# Waveform_Gen_V1_0.net
KiCad netlist of a schematic drawn in EAGLE
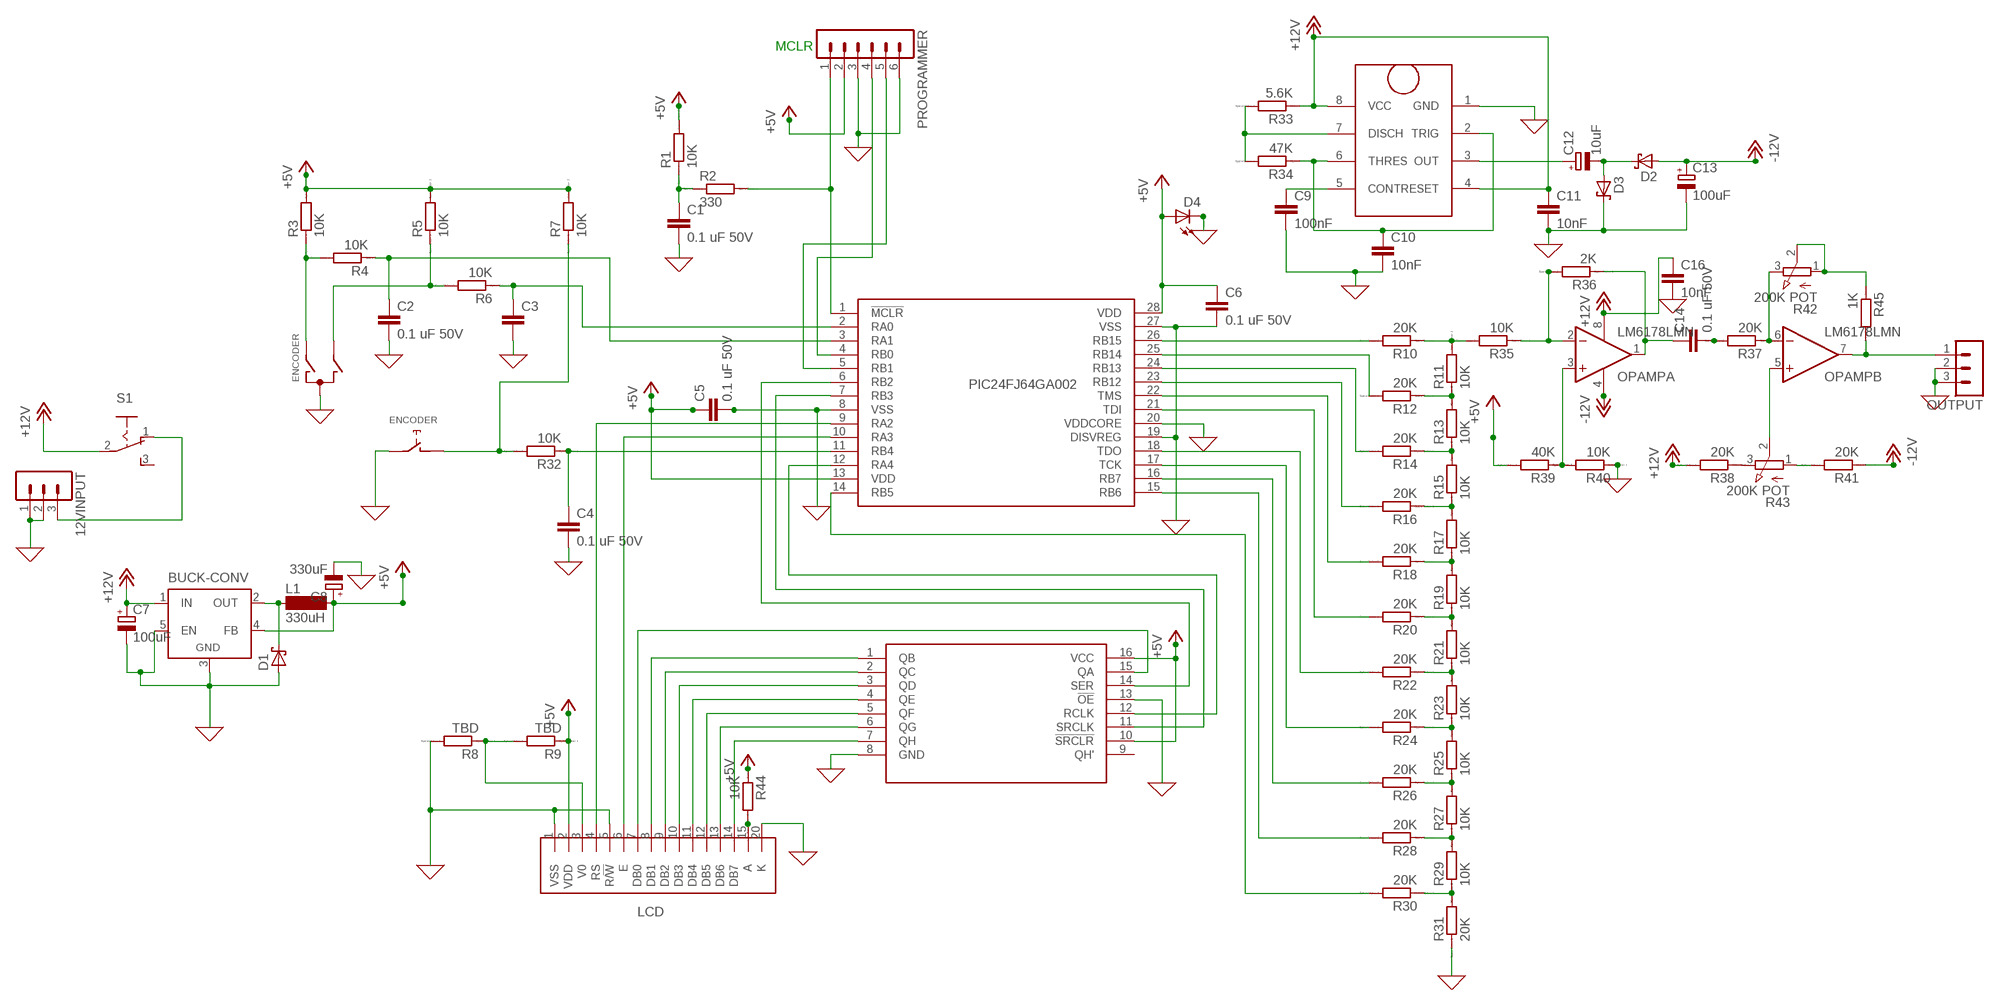
[diagram p0: schematic, sheet 1]

(export (version "E")
  (design (tool "Eeschema 10.0.6"))
  (components
    (comp (ref "12VINPUT")
      (value "MA03-1")
      (footprint "eagle-import:MA03-1")
      (libsource (lib "eagle-import") (part "MA03-1"))
    )
    (comp (ref "BUCK-CONV")
      (value "LM2596TH")
      (footprint "eagle-import:TO220-52")
      (libsource (lib "eagle-import") (part "LM2596TH"))
    )
    (comp (ref "C1")
      (value "0.1 uF 50V")
      (footprint "eagle-import:C5B2.5")
      (libsource (lib "eagle-import") (part "C5/2.5"))
    )
    (comp (ref "C2")
      (value "0.1 uF 50V")
      (footprint "eagle-import:C5B2.5")
      (libsource (lib "eagle-import") (part "C5/2.5"))
    )
    (comp (ref "C3")
      (value "C5/2.5")
      (footprint "eagle-import:C5B2.5")
      (libsource (lib "eagle-import") (part "C5/2.5"))
    )
    (comp (ref "C4")
      (value "0.1 uF 50V")
      (footprint "eagle-import:C5B2.5")
      (libsource (lib "eagle-import") (part "C5/2.5"))
    )
    (comp (ref "C5")
      (value "0.1 uF 50V")
      (footprint "eagle-import:C5B2.5")
      (libsource (lib "eagle-import") (part "C5/2.5"))
    )
    (comp (ref "C6")
      (value "0.1 uF 50V")
      (footprint "eagle-import:C5B2.5")
      (libsource (lib "eagle-import") (part "C5/2.5"))
    )
    (comp (ref "C7")
      (value "100uF")
      (footprint "eagle-import:E3,5-8")
      (libsource (lib "eagle-import") (part "CPOL-EUE3.5-8"))
    )
    (comp (ref "C8")
      (value "330uF")
      (footprint "eagle-import:E3,5-10")
      (libsource (lib "eagle-import") (part "CPOL-EUE3.5-10"))
    )
    (comp (ref "C9")
      (value "100nF")
      (footprint "eagle-import:C5B2.5")
      (libsource (lib "eagle-import") (part "C5/2.5"))
    )
    (comp (ref "C10")
      (value "10nF")
      (footprint "eagle-import:C5B2.5")
      (libsource (lib "eagle-import") (part "C5/2.5"))
    )
    (comp (ref "C11")
      (value "10nF")
      (footprint "eagle-import:C5B2.5")
      (libsource (lib "eagle-import") (part "C5/2.5"))
    )
    (comp (ref "C12")
      (value "10uF")
      (footprint "eagle-import:E2,5-6E")
      (libsource (lib "eagle-import") (part "CPOL-EUE2,5-6E"))
    )
    (comp (ref "C13")
      (value "100uF")
      (footprint "eagle-import:E3,5-8")
      (libsource (lib "eagle-import") (part "CPOL-EUE3.5-8"))
    )
    (comp (ref "C14")
      (value "0.1 uF 50V")
      (footprint "eagle-import:C5B2.5")
      (libsource (lib "eagle-import") (part "C5/2.5"))
    )
    (comp (ref "C16")
      (value "10nF")
      (footprint "eagle-import:C5B2.5")
      (libsource (lib "eagle-import") (part "C5/2.5"))
    )
    (comp (ref "D1")
      (value "SCHOTTKY-DIODETO92H")
      (footprint "eagle-import:TO92H")
      (libsource (lib "eagle-import") (part "SCHOTTKY-DIODETO92H"))
    )
    (comp (ref "D2")
      (value "SCHOTTKY-DIODETO92H")
      (footprint "eagle-import:TO92H")
      (libsource (lib "eagle-import") (part "SCHOTTKY-DIODETO92H"))
    )
    (comp (ref "D3")
      (value "SCHOTTKY-DIODETO92H")
      (footprint "eagle-import:TO92H")
      (libsource (lib "eagle-import") (part "SCHOTTKY-DIODETO92H"))
    )
    (comp (ref "D4")
      (value "SFH482")
      (footprint "eagle-import:SFH482")
      (libsource (lib "eagle-import") (part "SFH482"))
    )
    (comp (ref "ENCODER")
      (value "EC12E_SW")
      (footprint "eagle-import:ALPS_EC12E_SW")
      (fields (field (name "MPN") "EC12E2424407"))
      (libsource (lib "eagle-import") (part "EC12E_SW"))
    )
    (comp (ref "IC555")
      (value "IC555")
      (footprint "eagle-import:DIL08")
      (libsource (lib "eagle-import") (part "IC555"))
    )
    (comp (ref "L1")
      (value "330uH")
      (footprint "eagle-import:SD12K100")
      (libsource (lib "eagle-import") (part "SD12K100"))
    )
    (comp (ref "LCD")
      (value "LCD_PIN")
      (footprint "eagle-import:SIL16")
      (libsource (lib "eagle-import") (part "LCD_PIN"))
    )
    (comp (ref "OPAMP")
      (value "LM6178LMN")
      (footprint "eagle-import:DIL08")
      (libsource (lib "eagle-import") (part "LM6178NLM"))
    )
    (comp (ref "OUTPUT")
      (value "MA03-1")
      (footprint "eagle-import:MA03-1")
      (libsource (lib "eagle-import") (part "MA03-1"))
    )
    (comp (ref "PIC24FJ64GA002")
      (value "PIC24FJ64GA002")
      (footprint "eagle-import:DIL28-3")
      (fields (field (name "MPN") "PIC24FJ64GA002-I/SP"))
      (libsource (lib "eagle-import") (part "PIC24FJ64GA002"))
    )
    (comp (ref "PROGRAMMER")
      (value "MA06-1")
      (footprint "eagle-import:MA06-1")
      (libsource (lib "eagle-import") (part "MA06-1"))
    )
    (comp (ref "R1")
      (value "10K")
      (footprint "eagle-import:0207_10")
      (libsource (lib "eagle-import") (part "R0207/10"))
    )
    (comp (ref "R2")
      (value "330")
      (footprint "eagle-import:0207_10")
      (libsource (lib "eagle-import") (part "R0207/10"))
    )
    (comp (ref "R3")
      (value "10K")
      (footprint "eagle-import:0207_10")
      (libsource (lib "eagle-import") (part "R0207/10"))
    )
    (comp (ref "R4")
      (value "10K")
      (footprint "eagle-import:0207_10")
      (libsource (lib "eagle-import") (part "R0207/10"))
    )
    (comp (ref "R5")
      (value "10K")
      (footprint "eagle-import:0207_10")
      (libsource (lib "eagle-import") (part "R0207/10"))
    )
    (comp (ref "R6")
      (value "10K")
      (footprint "eagle-import:0207_10")
      (libsource (lib "eagle-import") (part "R0207/10"))
    )
    (comp (ref "R7")
      (value "10K")
      (footprint "eagle-import:0207_10")
      (libsource (lib "eagle-import") (part "R0207/10"))
    )
    (comp (ref "R8")
      (value "TBD")
      (footprint "eagle-import:0207_10")
      (libsource (lib "eagle-import") (part "R0207/10"))
    )
    (comp (ref "R9")
      (value "TBD")
      (footprint "eagle-import:0207_10")
      (libsource (lib "eagle-import") (part "R0207/10"))
    )
    (comp (ref "R10")
      (value "20K")
      (footprint "eagle-import:0207_10")
      (libsource (lib "eagle-import") (part "R0207/10"))
    )
    (comp (ref "R11")
      (value "10K")
      (footprint "eagle-import:0207_10")
      (libsource (lib "eagle-import") (part "R0207/10"))
    )
    (comp (ref "R12")
      (value "20K")
      (footprint "eagle-import:0207_10")
      (libsource (lib "eagle-import") (part "R0207/10"))
    )
    (comp (ref "R13")
      (value "10K")
      (footprint "eagle-import:0207_10")
      (libsource (lib "eagle-import") (part "R0207/10"))
    )
    (comp (ref "R14")
      (value "20K")
      (footprint "eagle-import:0207_10")
      (libsource (lib "eagle-import") (part "R0207/10"))
    )
    (comp (ref "R15")
      (value "10K")
      (footprint "eagle-import:0207_10")
      (libsource (lib "eagle-import") (part "R0207/10"))
    )
    (comp (ref "R16")
      (value "20K")
      (footprint "eagle-import:0207_10")
      (libsource (lib "eagle-import") (part "R0207/10"))
    )
    (comp (ref "R17")
      (value "10K")
      (footprint "eagle-import:0207_10")
      (libsource (lib "eagle-import") (part "R0207/10"))
    )
    (comp (ref "R18")
      (value "20K")
      (footprint "eagle-import:0207_10")
      (libsource (lib "eagle-import") (part "R0207/10"))
    )
    (comp (ref "R19")
      (value "10K")
      (footprint "eagle-import:0207_10")
      (libsource (lib "eagle-import") (part "R0207/10"))
    )
    (comp (ref "R20")
      (value "20K")
      (footprint "eagle-import:0207_10")
      (libsource (lib "eagle-import") (part "R0207/10"))
    )
    (comp (ref "R21")
      (value "10K")
      (footprint "eagle-import:0207_10")
      (libsource (lib "eagle-import") (part "R0207/10"))
    )
    (comp (ref "R22")
      (value "20K")
      (footprint "eagle-import:0207_10")
      (libsource (lib "eagle-import") (part "R0207/10"))
    )
    (comp (ref "R23")
      (value "10K")
      (footprint "eagle-import:0207_10")
      (libsource (lib "eagle-import") (part "R0207/10"))
    )
    (comp (ref "R24")
      (value "20K")
      (footprint "eagle-import:0207_10")
      (libsource (lib "eagle-import") (part "R0207/10"))
    )
    (comp (ref "R25")
      (value "10K")
      (footprint "eagle-import:0207_10")
      (libsource (lib "eagle-import") (part "R0207/10"))
    )
    (comp (ref "R26")
      (value "20K")
      (footprint "eagle-import:0207_10")
      (libsource (lib "eagle-import") (part "R0207/10"))
    )
    (comp (ref "R27")
      (value "10K")
      (footprint "eagle-import:0207_10")
      (libsource (lib "eagle-import") (part "R0207/10"))
    )
    (comp (ref "R28")
      (value "20K")
      (footprint "eagle-import:0207_10")
      (libsource (lib "eagle-import") (part "R0207/10"))
    )
    (comp (ref "R29")
      (value "10K")
      (footprint "eagle-import:0207_10")
      (libsource (lib "eagle-import") (part "R0207/10"))
    )
    (comp (ref "R30")
      (value "20K")
      (footprint "eagle-import:0207_10")
      (libsource (lib "eagle-import") (part "R0207/10"))
    )
    (comp (ref "R31")
      (value "20K")
      (footprint "eagle-import:0207_10")
      (libsource (lib "eagle-import") (part "R0207/10"))
    )
    (comp (ref "R32")
      (value "10K")
      (footprint "eagle-import:0207_10")
      (libsource (lib "eagle-import") (part "R0207/10"))
    )
    (comp (ref "R33")
      (value "5.6K")
      (footprint "eagle-import:0207_10")
      (libsource (lib "eagle-import") (part "R0207/10"))
    )
    (comp (ref "R34")
      (value "47K")
      (footprint "eagle-import:0207_10")
      (libsource (lib "eagle-import") (part "R0207/10"))
    )
    (comp (ref "R35")
      (value "10K")
      (footprint "eagle-import:0207_10")
      (libsource (lib "eagle-import") (part "R0207/10"))
    )
    (comp (ref "R36")
      (value "2K")
      (footprint "eagle-import:0207_10")
      (libsource (lib "eagle-import") (part "R0207/10"))
    )
    (comp (ref "R37")
      (value "20K")
      (footprint "eagle-import:0207_10")
      (libsource (lib "eagle-import") (part "R0207/10"))
    )
    (comp (ref "R38")
      (value "20K")
      (footprint "eagle-import:0207_10")
      (libsource (lib "eagle-import") (part "R0207/10"))
    )
    (comp (ref "R39")
      (value "40K")
      (footprint "eagle-import:0207_10")
      (libsource (lib "eagle-import") (part "R0207/10"))
    )
    (comp (ref "R40")
      (value "10K")
      (footprint "eagle-import:0207_10")
      (libsource (lib "eagle-import") (part "R0207/10"))
    )
    (comp (ref "R41")
      (value "20K")
      (footprint "eagle-import:0207_10")
      (libsource (lib "eagle-import") (part "R0207/10"))
    )
    (comp (ref "R42")
      (value "200K POT")
      (footprint "eagle-import:EVUF")
      (libsource (lib "eagle-import") (part "EVUAF2"))
    )
    (comp (ref "R43")
      (value "200K POT")
      (footprint "eagle-import:EVUF")
      (libsource (lib "eagle-import") (part "EVUAF2"))
    )
    (comp (ref "R44")
      (value "10K")
      (footprint "eagle-import:0207_10")
      (libsource (lib "eagle-import") (part "R0207/10"))
    )
    (comp (ref "R45")
      (value "1K")
      (footprint "eagle-import:0207_10")
      (libsource (lib "eagle-import") (part "R0207/10"))
    )
    (comp (ref "S1")
      (value "255SB")
      (footprint "eagle-import:255SB")
      (libsource (lib "eagle-import") (part "255SB"))
    )
    (comp (ref "SHIFT-REG")
      (value "74HC595")
      (footprint "eagle-import:DIL16")
      (libsource (lib "eagle-import") (part "74HC595"))
    )
  )
  (nets
    (net (code "1") (name "+5V") (class "Default")
      (node (ref "BUCK-CONV") (pin "4") (pinfunction "FB_4") (pintype "input"))
      (node (ref "C5") (pin "1") (pinfunction "1_1") (pintype "passive"))
      (node (ref "C6") (pin "1") (pinfunction "1_1") (pintype "passive"))
      (node (ref "C8") (pin "+") (pinfunction "+_+") (pintype "passive"))
      (node (ref "D4") (pin "A") (pinfunction "A_A") (pintype "passive"))
      (node (ref "L1") (pin "2") (pinfunction "2_2") (pintype "passive"))
      (node (ref "LCD") (pin "2") (pinfunction "VDD_2") (pintype "bidirectional"))
      (node (ref "PIC24FJ64GA002") (pin "13") (pinfunction "VDD_13") (pintype "power_in"))
      (node (ref "PIC24FJ64GA002") (pin "28") (pinfunction "VDD_28") (pintype "power_in"))
      (node (ref "PROGRAMMER") (pin "2") (pinfunction "2_2") (pintype "passive"))
      (node (ref "R1") (pin "2") (pinfunction "2_2") (pintype "passive"))
      (node (ref "R3") (pin "2") (pinfunction "2_2") (pintype "passive"))
      (node (ref "R39") (pin "2") (pinfunction "2_2") (pintype "passive"))
      (node (ref "R44") (pin "1") (pinfunction "1_1") (pintype "passive"))
      (node (ref "R5") (pin "2") (pinfunction "2_2") (pintype "passive"))
      (node (ref "R7") (pin "2") (pinfunction "2_2") (pintype "passive"))
      (node (ref "R9") (pin "1") (pinfunction "1_1") (pintype "passive"))
      (node (ref "SHIFT-REG") (pin "10") (pinfunction "~{SRCLR}_10") (pintype "bidirectional"))
      (node (ref "SHIFT-REG") (pin "16") (pinfunction "VCC_16") (pintype "bidirectional"))
    )
    (net (code "2") (name "+12V") (class "Default")
      (node (ref "BUCK-CONV") (pin "1") (pinfunction "IN_1") (pintype "input"))
      (node (ref "C11") (pin "1") (pinfunction "1_1") (pintype "passive"))
      (node (ref "C16") (pin "1") (pinfunction "1_1") (pintype "passive"))
      (node (ref "C7") (pin "+") (pinfunction "+_+") (pintype "passive"))
      (node (ref "IC555") (pin "4") (pinfunction "RESET_4") (pintype "bidirectional"))
      (node (ref "IC555") (pin "8") (pinfunction "VCC_8") (pintype "bidirectional"))
      (node (ref "OPAMP") (pin "8") (pinfunction "V+_8") (pintype "power_in"))
      (node (ref "R33") (pin "1") (pinfunction "1_1") (pintype "passive"))
      (node (ref "R38") (pin "2") (pinfunction "2_2") (pintype "passive"))
      (node (ref "S1") (pin "2") (pinfunction "P_2") (pintype "passive"))
    )
    (net (code "3") (name "-12V") (class "Default")
      (node (ref "C13") (pin "+") (pinfunction "+_+") (pintype "passive"))
      (node (ref "D2") (pin "1") (pinfunction "A_1") (pintype "passive"))
      (node (ref "OPAMP") (pin "4") (pinfunction "V-_4") (pintype "power_in"))
      (node (ref "R41") (pin "1") (pinfunction "1_1") (pintype "passive"))
    )
    (net (code "4") (name "GND") (class "Default")
      (node (ref "12VINPUT") (pin "1") (pinfunction "1_1") (pintype "passive"))
      (node (ref "12VINPUT") (pin "2") (pinfunction "2_2") (pintype "passive"))
      (node (ref "BUCK-CONV") (pin "3") (pinfunction "GND_3") (pintype "power_in"))
      (node (ref "BUCK-CONV") (pin "5") (pinfunction "EN_5") (pintype "input"))
      (node (ref "C1") (pin "2") (pinfunction "2_2") (pintype "passive"))
      (node (ref "C10") (pin "2") (pinfunction "2_2") (pintype "passive"))
      (node (ref "C11") (pin "2") (pinfunction "2_2") (pintype "passive"))
      (node (ref "C13") (pin "-") (pinfunction "-_-") (pintype "passive"))
      (node (ref "C16") (pin "2") (pinfunction "2_2") (pintype "passive"))
      (node (ref "C2") (pin "2") (pinfunction "2_2") (pintype "passive"))
      (node (ref "C3") (pin "2") (pinfunction "2_2") (pintype "passive"))
      (node (ref "C4") (pin "2") (pinfunction "2_2") (pintype "passive"))
      (node (ref "C5") (pin "2") (pinfunction "2_2") (pintype "passive"))
      (node (ref "C6") (pin "2") (pinfunction "2_2") (pintype "passive"))
      (node (ref "C7") (pin "-") (pinfunction "-_-") (pintype "passive"))
      (node (ref "C8") (pin "-") (pinfunction "-_-") (pintype "passive"))
      (node (ref "C9") (pin "2") (pinfunction "2_2") (pintype "passive"))
      (node (ref "D1") (pin "1") (pinfunction "A_1") (pintype "passive"))
      (node (ref "D3") (pin "2") (pinfunction "C_2") (pintype "passive"))
      (node (ref "D4") (pin "K") (pinfunction "C_K") (pintype "passive"))
      (node (ref "ENCODER") (pin "C") (pinfunction "C_C") (pintype "passive"))
      (node (ref "ENCODER") (pin "E") (pinfunction "2_E") (pintype "passive"))
      (node (ref "IC555") (pin "1") (pinfunction "GND_1") (pintype "bidirectional"))
      (node (ref "LCD") (pin "1") (pinfunction "VSS_1") (pintype "bidirectional"))
      (node (ref "LCD") (pin "20") (pinfunction "K_20") (pintype "bidirectional"))
      (node (ref "LCD") (pin "5") (pinfunction "R/~{W}_5") (pintype "bidirectional"))
      (node (ref "OUTPUT") (pin "2") (pinfunction "2_2") (pintype "passive"))
      (node (ref "OUTPUT") (pin "3") (pinfunction "3_3") (pintype "passive"))
      (node (ref "PIC24FJ64GA002") (pin "19") (pinfunction "DISVREG_19") (pintype "passive"))
      (node (ref "PIC24FJ64GA002") (pin "20") (pinfunction "VDDCORE_20") (pintype "power_in"))
      (node (ref "PIC24FJ64GA002") (pin "27") (pinfunction "VSS_27") (pintype "power_in"))
      (node (ref "PIC24FJ64GA002") (pin "8") (pinfunction "VSS_8") (pintype "power_in"))
      (node (ref "PROGRAMMER") (pin "3") (pinfunction "3_3") (pintype "passive"))
      (node (ref "PROGRAMMER") (pin "6") (pinfunction "6_6") (pintype "passive"))
      (node (ref "R31") (pin "1") (pinfunction "1_1") (pintype "passive"))
      (node (ref "R40") (pin "1") (pinfunction "1_1") (pintype "passive"))
      (node (ref "R8") (pin "2") (pinfunction "2_2") (pintype "passive"))
      (node (ref "SHIFT-REG") (pin "13") (pinfunction "~{OE}_13") (pintype "bidirectional"))
      (node (ref "SHIFT-REG") (pin "8") (pinfunction "GND_8") (pintype "bidirectional"))
    )
    (net (code "5") (name "Net-(BUCK-CONV-OUT)") (class "Default")
      (node (ref "BUCK-CONV") (pin "2") (pinfunction "OUT_2") (pintype "output"))
      (node (ref "D1") (pin "2") (pinfunction "C_2") (pintype "passive"))
      (node (ref "L1") (pin "1") (pinfunction "1_1") (pintype "passive"))
    )
    (net (code "6") (name "Net-(C1-Pad1)") (class "Default")
      (node (ref "C1") (pin "1") (pinfunction "1_1") (pintype "passive"))
      (node (ref "R1") (pin "1") (pinfunction "1_1") (pintype "passive"))
      (node (ref "R2") (pin "1") (pinfunction "1_1") (pintype "passive"))
    )
    (net (code "7") (name "Net-(C14-Pad2)") (class "Default")
      (node (ref "C14") (pin "2") (pinfunction "2_2") (pintype "passive"))
      (node (ref "R37") (pin "2") (pinfunction "2_2") (pintype "passive"))
    )
    (net (code "8") (name "Net-(D2-C)") (class "Default")
      (node (ref "C12") (pin "-") (pinfunction "-_-") (pintype "passive"))
      (node (ref "D2") (pin "2") (pinfunction "C_2") (pintype "passive"))
      (node (ref "D3") (pin "1") (pinfunction "A_1") (pintype "passive"))
    )
    (net (code "9") (name "Net-(ENCODER-PadA)") (class "Default")
      (node (ref "ENCODER") (pin "A") (pinfunction "A_A") (pintype "passive"))
      (node (ref "R3") (pin "1") (pinfunction "1_1") (pintype "passive"))
      (node (ref "R4") (pin "2") (pinfunction "2_2") (pintype "passive"))
    )
    (net (code "10") (name "Net-(ENCODER-PadB)") (class "Default")
      (node (ref "ENCODER") (pin "B") (pinfunction "B_B") (pintype "passive"))
      (node (ref "R5") (pin "1") (pinfunction "1_1") (pintype "passive"))
      (node (ref "R6") (pin "2") (pinfunction "2_2") (pintype "passive"))
    )
    (net (code "11") (name "Net-(ENCODERB-1)") (class "Default")
      (node (ref "ENCODER") (pin "D") (pinfunction "1_D") (pintype "passive"))
      (node (ref "R32") (pin "2") (pinfunction "2_2") (pintype "passive"))
      (node (ref "R7") (pin "1") (pinfunction "1_1") (pintype "passive"))
    )
    (net (code "12") (name "Net-(IC555-CONT)") (class "Default")
      (node (ref "C9") (pin "1") (pinfunction "1_1") (pintype "passive"))
      (node (ref "IC555") (pin "5") (pinfunction "CONT_5") (pintype "bidirectional"))
    )
    (net (code "13") (name "Net-(IC555-DISCH)") (class "Default")
      (node (ref "IC555") (pin "7") (pinfunction "DISCH_7") (pintype "bidirectional"))
      (node (ref "R33") (pin "2") (pinfunction "2_2") (pintype "passive"))
      (node (ref "R34") (pin "2") (pinfunction "2_2") (pintype "passive"))
    )
    (net (code "14") (name "Net-(IC555-OUT)") (class "Default")
      (node (ref "C12") (pin "+") (pinfunction "+_+") (pintype "passive"))
      (node (ref "IC555") (pin "3") (pinfunction "OUT_3") (pintype "bidirectional"))
    )
    (net (code "15") (name "Net-(IC555-THRES)") (class "Default")
      (node (ref "C10") (pin "1") (pinfunction "1_1") (pintype "passive"))
      (node (ref "IC555") (pin "2") (pinfunction "TRIG_2") (pintype "bidirectional"))
      (node (ref "IC555") (pin "6") (pinfunction "THRES_6") (pintype "bidirectional"))
      (node (ref "R34") (pin "1") (pinfunction "1_1") (pintype "passive"))
    )
    (net (code "16") (name "Net-(LCD-A)") (class "Default")
      (node (ref "LCD") (pin "15") (pinfunction "A_15") (pintype "bidirectional"))
      (node (ref "R44") (pin "2") (pinfunction "2_2") (pintype "passive"))
    )
    (net (code "17") (name "Net-(LCD-DB0)") (class "Default")
      (node (ref "LCD") (pin "7") (pinfunction "DB0_7") (pintype "bidirectional"))
      (node (ref "SHIFT-REG") (pin "15") (pinfunction "QA_15") (pintype "bidirectional"))
    )
    (net (code "18") (name "Net-(LCD-DB1)") (class "Default")
      (node (ref "LCD") (pin "8") (pinfunction "DB1_8") (pintype "bidirectional"))
      (node (ref "SHIFT-REG") (pin "1") (pinfunction "QB_1") (pintype "bidirectional"))
    )
    (net (code "19") (name "Net-(LCD-DB2)") (class "Default")
      (node (ref "LCD") (pin "9") (pinfunction "DB2_9") (pintype "bidirectional"))
      (node (ref "SHIFT-REG") (pin "2") (pinfunction "QC_2") (pintype "bidirectional"))
    )
    (net (code "20") (name "Net-(LCD-DB3)") (class "Default")
      (node (ref "LCD") (pin "10") (pinfunction "DB3_10") (pintype "bidirectional"))
      (node (ref "SHIFT-REG") (pin "3") (pinfunction "QD_3") (pintype "bidirectional"))
    )
    (net (code "21") (name "Net-(LCD-DB4)") (class "Default")
      (node (ref "LCD") (pin "11") (pinfunction "DB4_11") (pintype "bidirectional"))
      (node (ref "SHIFT-REG") (pin "4") (pinfunction "QE_4") (pintype "bidirectional"))
    )
    (net (code "22") (name "Net-(LCD-DB5)") (class "Default")
      (node (ref "LCD") (pin "12") (pinfunction "DB5_12") (pintype "bidirectional"))
      (node (ref "SHIFT-REG") (pin "5") (pinfunction "QF_5") (pintype "bidirectional"))
    )
    (net (code "23") (name "Net-(LCD-DB6)") (class "Default")
      (node (ref "LCD") (pin "13") (pinfunction "DB6_13") (pintype "bidirectional"))
      (node (ref "SHIFT-REG") (pin "6") (pinfunction "QG_6") (pintype "bidirectional"))
    )
    (net (code "24") (name "Net-(LCD-DB7)") (class "Default")
      (node (ref "LCD") (pin "14") (pinfunction "DB7_14") (pintype "bidirectional"))
      (node (ref "SHIFT-REG") (pin "7") (pinfunction "QH_7") (pintype "bidirectional"))
    )
    (net (code "25") (name "Net-(LCD-E)") (class "Default")
      (node (ref "LCD") (pin "6") (pinfunction "E_6") (pintype "bidirectional"))
      (node (ref "PIC24FJ64GA002") (pin "10") (pinfunction "RA3_10") (pintype "bidirectional"))
    )
    (net (code "26") (name "Net-(LCD-RS)") (class "Default")
      (node (ref "LCD") (pin "4") (pinfunction "RS_4") (pintype "bidirectional"))
      (node (ref "PIC24FJ64GA002") (pin "9") (pinfunction "RA2_9") (pintype "bidirectional"))
    )
    (net (code "27") (name "Net-(LCD-V0)") (class "Default")
      (node (ref "LCD") (pin "3") (pinfunction "V0_3") (pintype "bidirectional"))
      (node (ref "R8") (pin "1") (pinfunction "1_1") (pintype "passive"))
      (node (ref "R9") (pin "2") (pinfunction "2_2") (pintype "passive"))
    )
    (net (code "28") (name "Net-(OPAMPA-+IN)") (class "Default")
      (node (ref "OPAMP") (pin "3") (pinfunction "+IN_3") (pintype "input"))
      (node (ref "R39") (pin "1") (pinfunction "1_1") (pintype "passive"))
      (node (ref "R40") (pin "2") (pinfunction "2_2") (pintype "passive"))
    )
    (net (code "29") (name "Net-(OPAMPA--IN)") (class "Default")
      (node (ref "OPAMP") (pin "2") (pinfunction "-IN_2") (pintype "input"))
      (node (ref "R35") (pin "1") (pinfunction "1_1") (pintype "passive"))
      (node (ref "R36") (pin "2") (pinfunction "2_2") (pintype "passive"))
    )
    (net (code "30") (name "Net-(OPAMPA-OUT)") (class "Default")
      (node (ref "C14") (pin "1") (pinfunction "1_1") (pintype "passive"))
      (node (ref "OPAMP") (pin "1") (pinfunction "OUT_1") (pintype "output"))
      (node (ref "R36") (pin "1") (pinfunction "1_1") (pintype "passive"))
    )
    (net (code "31") (name "Net-(OPAMPB-+IN)") (class "Default")
      (node (ref "OPAMP") (pin "5") (pinfunction "+IN_5") (pintype "input"))
      (node (ref "R43") (pin "2") (pinfunction "S_2") (pintype "passive"))
    )
    (net (code "32") (name "Net-(OPAMPB--IN)") (class "Default")
      (node (ref "OPAMP") (pin "6") (pinfunction "-IN_6") (pintype "input"))
      (node (ref "R37") (pin "1") (pinfunction "1_1") (pintype "passive"))
      (node (ref "R42") (pin "3") (pinfunction "E_3") (pintype "passive"))
    )
    (net (code "33") (name "Net-(OPAMPB-OUT)") (class "Default")
      (node (ref "OPAMP") (pin "7") (pinfunction "OUT_7") (pintype "output"))
      (node (ref "OUTPUT") (pin "1") (pinfunction "1_1") (pintype "passive"))
      (node (ref "R45") (pin "2") (pinfunction "2_2") (pintype "passive"))
    )
    (net (code "34") (name "Net-(PIC24FJ64GA002-RA0)") (class "Default")
      (node (ref "C3") (pin "1") (pinfunction "1_1") (pintype "passive"))
      (node (ref "PIC24FJ64GA002") (pin "2") (pinfunction "RA0_2") (pintype "bidirectional"))
      (node (ref "R6") (pin "1") (pinfunction "1_1") (pintype "passive"))
    )
    (net (code "35") (name "Net-(PIC24FJ64GA002-RA1)") (class "Default")
      (node (ref "C2") (pin "1") (pinfunction "1_1") (pintype "passive"))
      (node (ref "PIC24FJ64GA002") (pin "3") (pinfunction "RA1_3") (pintype "bidirectional"))
      (node (ref "R4") (pin "1") (pinfunction "1_1") (pintype "passive"))
    )
    (net (code "36") (name "Net-(PIC24FJ64GA002-RA4)") (class "Default")
      (node (ref "PIC24FJ64GA002") (pin "12") (pinfunction "RA4_12") (pintype "bidirectional"))
      (node (ref "SHIFT-REG") (pin "12") (pinfunction "RCLK_12") (pintype "bidirectional"))
    )
    (net (code "37") (name "Net-(PIC24FJ64GA002-RB0)") (class "Default")
      (node (ref "PIC24FJ64GA002") (pin "4") (pinfunction "RB0_4") (pintype "bidirectional"))
      (node (ref "PROGRAMMER") (pin "4") (pinfunction "4_4") (pintype "passive"))
    )
    (net (code "38") (name "Net-(PIC24FJ64GA002-RB1)") (class "Default")
      (node (ref "PIC24FJ64GA002") (pin "5") (pinfunction "RB1_5") (pintype "bidirectional"))
      (node (ref "PROGRAMMER") (pin "5") (pinfunction "5_5") (pintype "passive"))
    )
    (net (code "39") (name "Net-(PIC24FJ64GA002-RB2)") (class "Default")
      (node (ref "PIC24FJ64GA002") (pin "6") (pinfunction "RB2_6") (pintype "bidirectional"))
      (node (ref "SHIFT-REG") (pin "14") (pinfunction "SER_14") (pintype "bidirectional"))
    )
    (net (code "40") (name "Net-(PIC24FJ64GA002-RB3)") (class "Default")
      (node (ref "PIC24FJ64GA002") (pin "7") (pinfunction "RB3_7") (pintype "bidirectional"))
      (node (ref "SHIFT-REG") (pin "11") (pinfunction "SRCLK_11") (pintype "bidirectional"))
    )
    (net (code "41") (name "Net-(PIC24FJ64GA002-RB4)") (class "Default")
      (node (ref "C4") (pin "1") (pinfunction "1_1") (pintype "passive"))
      (node (ref "PIC24FJ64GA002") (pin "11") (pinfunction "RB4_11") (pintype "bidirectional"))
      (node (ref "R32") (pin "1") (pinfunction "1_1") (pintype "passive"))
    )
    (net (code "42") (name "Net-(PIC24FJ64GA002-RB5)") (class "Default")
      (node (ref "PIC24FJ64GA002") (pin "14") (pinfunction "RB5_14") (pintype "bidirectional"))
      (node (ref "R30") (pin "2") (pinfunction "2_2") (pintype "passive"))
    )
    (net (code "43") (name "Net-(PIC24FJ64GA002-RB6)") (class "Default")
      (node (ref "PIC24FJ64GA002") (pin "15") (pinfunction "RB6_15") (pintype "bidirectional"))
      (node (ref "R28") (pin "2") (pinfunction "2_2") (pintype "passive"))
    )
    (net (code "44") (name "Net-(PIC24FJ64GA002-RB7)") (class "Default")
      (node (ref "PIC24FJ64GA002") (pin "16") (pinfunction "RB7_16") (pintype "bidirectional"))
      (node (ref "R26") (pin "2") (pinfunction "2_2") (pintype "passive"))
    )
    (net (code "45") (name "Net-(PIC24FJ64GA002-RB12)") (class "Default")
      (node (ref "PIC24FJ64GA002") (pin "23") (pinfunction "RB12_23") (pintype "bidirectional"))
      (node (ref "R16") (pin "2") (pinfunction "2_2") (pintype "passive"))
    )
    (net (code "46") (name "Net-(PIC24FJ64GA002-RB13)") (class "Default")
      (node (ref "PIC24FJ64GA002") (pin "24") (pinfunction "RB13_24") (pintype "bidirectional"))
      (node (ref "R14") (pin "2") (pinfunction "2_2") (pintype "passive"))
    )
    (net (code "47") (name "Net-(PIC24FJ64GA002-RB14)") (class "Default")
      (node (ref "PIC24FJ64GA002") (pin "25") (pinfunction "RB14_25") (pintype "bidirectional"))
      (node (ref "R12") (pin "2") (pinfunction "2_2") (pintype "passive"))
    )
    (net (code "48") (name "Net-(PIC24FJ64GA002-RB15)") (class "Default")
      (node (ref "PIC24FJ64GA002") (pin "26") (pinfunction "RB15_26") (pintype "bidirectional"))
      (node (ref "R10") (pin "2") (pinfunction "2_2") (pintype "passive"))
    )
    (net (code "49") (name "Net-(PIC24FJ64GA002-TCK)") (class "Default")
      (node (ref "PIC24FJ64GA002") (pin "17") (pinfunction "TCK_17") (pintype "input"))
      (node (ref "R24") (pin "2") (pinfunction "2_2") (pintype "passive"))
    )
    (net (code "50") (name "Net-(PIC24FJ64GA002-TDI)") (class "Default")
      (node (ref "PIC24FJ64GA002") (pin "21") (pinfunction "TDI_21") (pintype "input"))
      (node (ref "R20") (pin "2") (pinfunction "2_2") (pintype "passive"))
    )
    (net (code "51") (name "Net-(PIC24FJ64GA002-TDO)") (class "Default")
      (node (ref "PIC24FJ64GA002") (pin "18") (pinfunction "TDO_18") (pintype "output"))
      (node (ref "R22") (pin "2") (pinfunction "2_2") (pintype "passive"))
    )
    (net (code "52") (name "Net-(PIC24FJ64GA002-TMS)") (class "Default")
      (node (ref "PIC24FJ64GA002") (pin "22") (pinfunction "TMS_22") (pintype "input"))
      (node (ref "R18") (pin "2") (pinfunction "2_2") (pintype "passive"))
    )
    (net (code "53") (name "Net-(PIC24FJ64GA002-~{MCLR})") (class "Default")
      (node (ref "PIC24FJ64GA002") (pin "1") (pinfunction "~{MCLR}_1") (pintype "bidirectional"))
      (node (ref "PROGRAMMER") (pin "1") (pinfunction "1_1") (pintype "passive"))
      (node (ref "R2") (pin "2") (pinfunction "2_2") (pintype "passive"))
    )
    (net (code "54") (name "Net-(R10-Pad1)") (class "Default")
      (node (ref "R10") (pin "1") (pinfunction "1_1") (pintype "passive"))
      (node (ref "R11") (pin "2") (pinfunction "2_2") (pintype "passive"))
      (node (ref "R35") (pin "2") (pinfunction "2_2") (pintype "passive"))
    )
    (net (code "55") (name "Net-(R11-Pad1)") (class "Default")
      (node (ref "R11") (pin "1") (pinfunction "1_1") (pintype "passive"))
      (node (ref "R12") (pin "1") (pinfunction "1_1") (pintype "passive"))
      (node (ref "R13") (pin "2") (pinfunction "2_2") (pintype "passive"))
    )
    (net (code "56") (name "Net-(R13-Pad1)") (class "Default")
      (node (ref "R13") (pin "1") (pinfunction "1_1") (pintype "passive"))
      (node (ref "R14") (pin "1") (pinfunction "1_1") (pintype "passive"))
      (node (ref "R15") (pin "2") (pinfunction "2_2") (pintype "passive"))
    )
    (net (code "57") (name "Net-(R15-Pad1)") (class "Default")
      (node (ref "R15") (pin "1") (pinfunction "1_1") (pintype "passive"))
      (node (ref "R16") (pin "1") (pinfunction "1_1") (pintype "passive"))
      (node (ref "R17") (pin "2") (pinfunction "2_2") (pintype "passive"))
    )
    (net (code "58") (name "Net-(R17-Pad1)") (class "Default")
      (node (ref "R17") (pin "1") (pinfunction "1_1") (pintype "passive"))
      (node (ref "R18") (pin "1") (pinfunction "1_1") (pintype "passive"))
      (node (ref "R19") (pin "2") (pinfunction "2_2") (pintype "passive"))
    )
    (net (code "59") (name "Net-(R19-Pad1)") (class "Default")
      (node (ref "R19") (pin "1") (pinfunction "1_1") (pintype "passive"))
      (node (ref "R20") (pin "1") (pinfunction "1_1") (pintype "passive"))
      (node (ref "R21") (pin "2") (pinfunction "2_2") (pintype "passive"))
    )
    (net (code "60") (name "Net-(R21-Pad1)") (class "Default")
      (node (ref "R21") (pin "1") (pinfunction "1_1") (pintype "passive"))
      (node (ref "R22") (pin "1") (pinfunction "1_1") (pintype "passive"))
      (node (ref "R23") (pin "2") (pinfunction "2_2") (pintype "passive"))
    )
    (net (code "61") (name "Net-(R23-Pad1)") (class "Default")
      (node (ref "R23") (pin "1") (pinfunction "1_1") (pintype "passive"))
      (node (ref "R24") (pin "1") (pinfunction "1_1") (pintype "passive"))
      (node (ref "R25") (pin "2") (pinfunction "2_2") (pintype "passive"))
    )
    (net (code "62") (name "Net-(R25-Pad1)") (class "Default")
      (node (ref "R25") (pin "1") (pinfunction "1_1") (pintype "passive"))
      (node (ref "R26") (pin "1") (pinfunction "1_1") (pintype "passive"))
      (node (ref "R27") (pin "2") (pinfunction "2_2") (pintype "passive"))
    )
    (net (code "63") (name "Net-(R27-Pad1)") (class "Default")
      (node (ref "R27") (pin "1") (pinfunction "1_1") (pintype "passive"))
      (node (ref "R28") (pin "1") (pinfunction "1_1") (pintype "passive"))
      (node (ref "R29") (pin "2") (pinfunction "2_2") (pintype "passive"))
    )
    (net (code "64") (name "Net-(R29-Pad1)") (class "Default")
      (node (ref "R29") (pin "1") (pinfunction "1_1") (pintype "passive"))
      (node (ref "R30") (pin "1") (pinfunction "1_1") (pintype "passive"))
      (node (ref "R31") (pin "2") (pinfunction "2_2") (pintype "passive"))
    )
    (net (code "65") (name "Net-(R42-A)") (class "Default")
      (node (ref "R42") (pin "1") (pinfunction "A_1") (pintype "passive"))
      (node (ref "R42") (pin "2") (pinfunction "S_2") (pintype "passive"))
      (node (ref "R45") (pin "1") (pinfunction "1_1") (pintype "passive"))
    )
    (net (code "66") (name "Net-(R43-A)") (class "Default")
      (node (ref "R41") (pin "2") (pinfunction "2_2") (pintype "passive"))
      (node (ref "R43") (pin "1") (pinfunction "A_1") (pintype "passive"))
    )
    (net (code "67") (name "Net-(R43-E)") (class "Default")
      (node (ref "R38") (pin "1") (pinfunction "1_1") (pintype "passive"))
      (node (ref "R43") (pin "3") (pinfunction "E_3") (pintype "passive"))
    )
    (net (code "68") (name "Net-(S1-O)") (class "Default")
      (node (ref "12VINPUT") (pin "3") (pinfunction "3_3") (pintype "passive"))
      (node (ref "S1") (pin "1") (pinfunction "O_1") (pintype "passive"))
    )
    (net (code "69") (name "unconnected-(S1-S-Pad3)") (class "Default")
      (node (ref "S1") (pin "3") (pinfunction "S_3") (pintype "passive"))
    )
    (net (code "70") (name "unconnected-(SHIFT-REG-QH'-Pad9)") (class "Default")
      (node (ref "SHIFT-REG") (pin "9") (pinfunction "QH'_9") (pintype "bidirectional"))
    )
  )
)
